# series_noprotection.net
KiCad netlist of a schematic drawn in Altium Designer
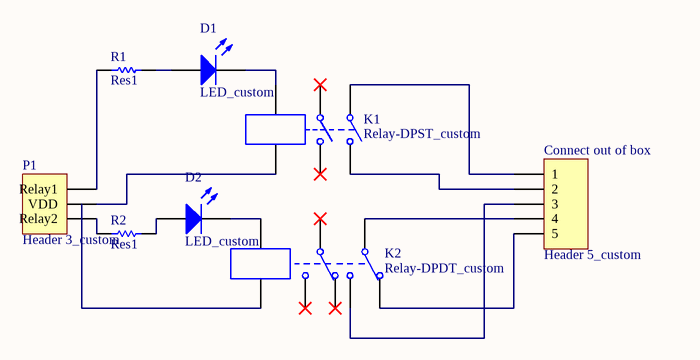
[diagram p0: series_noprotection.SchDoc]

(export (version "E")
  (design (tool "Eeschema 10.0.6"))
  (components
    (comp (ref "Connect out of box")
      (value "Header 5_custom")
      (footprint "PCB_Footprints:TE5")
      (description "Header, 5-Pin")
      (fields (field (name "PUBLISHER") "Altium Limited"))
      (libsource (lib "Integrated_Library_1") (part "Header 5_custom"))
    )
    (comp (ref "D1")
      (value "LED_custom")
      (footprint "PCB_Footprints:LED_Custom")
      (description "Typical INFRARED GaAs LED")
      (fields (field (name "PUBLISHER") "Altium Limited"))
      (libsource (lib "Integrated_Library_1") (part "LED_custom"))
    )
    (comp (ref "D2")
      (value "LED_custom")
      (footprint "PCB_Footprints:LED_Custom")
      (description "Typical INFRARED GaAs LED")
      (fields (field (name "PUBLISHER") "Altium Limited"))
      (libsource (lib "Integrated_Library_1") (part "LED_custom"))
    )
    (comp (ref "K1")
      (value "Relay-DPST_custom")
      (footprint "Relay-DPST_custom")
      (description "Dual-Pole Single-Throw Relay")
      (fields (field (name "PUBLISHER") "Altium Limited"))
      (libsource (lib "Integrated_Library_1") (part "Relay-DPST_custom"))
    )
    (comp (ref "K2")
      (value "Relay-DPDT_custom")
      (footprint "Relay-DPDT_custom")
      (description "Dual-Pole Dual-Throw Relay")
      (fields (field (name "PUBLISHER") "Altium Limited"))
      (libsource (lib "Integrated_Library_1") (part "Relay-DPDT_custom"))
    )
    (comp (ref "P1")
      (value "Header 3_custom")
      (footprint "PCB_Footprints:TB3")
      (description "Header, 3-Pin")
      (fields (field (name "PUBLISHER") "Altium Limited"))
      (libsource (lib "Integrated_Library_1") (part "Header 3_custom"))
    )
    (comp (ref "R1")
      (value "Res1")
      (footprint "AXIAL-0.3")
      (description "Resistor")
      (fields (field (name "PUBLISHER") "Altium Limited"))
      (libsource (lib "Miscellaneous Devices") (part "Res1"))
    )
    (comp (ref "R2")
      (value "Res1")
      (footprint "AXIAL-0.3")
      (description "Resistor")
      (fields (field (name "PUBLISHER") "Altium Limited"))
      (libsource (lib "Miscellaneous Devices") (part "Res1"))
    )
  )
  (nets
    (net (code "1") (name "Net-(Connect out of box-Pad1)") (class "Default")
      (node (ref "Connect out of box") (pin "1") (pinfunction "1_1") (pintype "passive"))
      (node (ref "K1") (pin "1") (pinfunction "1_1") (pintype "passive"))
    )
    (net (code "2") (name "Net-(Connect out of box-Pad2)") (class "Default")
      (node (ref "Connect out of box") (pin "2") (pinfunction "2_2") (pintype "passive"))
      (node (ref "K1") (pin "2") (pinfunction "2_2") (pintype "passive"))
    )
    (net (code "3") (name "Net-(Connect out of box-Pad3)") (class "Default")
      (node (ref "Connect out of box") (pin "3") (pinfunction "3_3") (pintype "passive"))
      (node (ref "K2") (pin "3") (pinfunction "3_3") (pintype "passive"))
    )
    (net (code "4") (name "Net-(Connect out of box-Pad4)") (class "Default")
      (node (ref "Connect out of box") (pin "4") (pinfunction "4_4") (pintype "passive"))
      (node (ref "K2") (pin "1") (pinfunction "1_1") (pintype "passive"))
    )
    (net (code "5") (name "Net-(Connect out of box-Pad5)") (class "Default")
      (node (ref "Connect out of box") (pin "5") (pinfunction "5_5") (pintype "passive"))
      (node (ref "K2") (pin "2") (pinfunction "2_2") (pintype "passive"))
    )
    (net (code "6") (name "Net-(D1-A)") (class "Default")
      (node (ref "D1") (pin "1") (pinfunction "A_1") (pintype "passive"))
      (node (ref "R1") (pin "1") (pinfunction "1_1") (pintype "passive"))
    )
    (net (code "7") (name "Net-(D1-K)") (class "Default")
      (node (ref "D1") (pin "2") (pinfunction "K_2") (pintype "passive"))
      (node (ref "K1") (pin "5") (pinfunction "5_5") (pintype "passive"))
    )
    (net (code "8") (name "Net-(D2-A)") (class "Default")
      (node (ref "D2") (pin "1") (pinfunction "A_1") (pintype "passive"))
      (node (ref "R2") (pin "1") (pinfunction "1_1") (pintype "passive"))
    )
    (net (code "9") (name "Net-(D2-K)") (class "Default")
      (node (ref "D2") (pin "2") (pinfunction "K_2") (pintype "passive"))
      (node (ref "K2") (pin "7") (pinfunction "7_7") (pintype "passive"))
    )
    (net (code "10") (name "Net-(P1-Relay1)") (class "Default")
      (node (ref "P1") (pin "3") (pinfunction "Relay1_3") (pintype "passive"))
      (node (ref "R1") (pin "2") (pinfunction "2_2") (pintype "passive"))
    )
    (net (code "11") (name "Net-(P1-Relay2)") (class "Default")
      (node (ref "P1") (pin "1") (pinfunction "Relay2_1") (pintype "passive"))
      (node (ref "R2") (pin "2") (pinfunction "2_2") (pintype "passive"))
    )
    (net (code "12") (name "Net-(P1-VDD)") (class "Default")
      (node (ref "K1") (pin "6") (pinfunction "6_6") (pintype "passive"))
      (node (ref "P1") (pin "2") (pinfunction "VDD_2") (pintype "passive"))
    )
    (net (code "13") (name "unconnected-(K1-Pad3)") (class "Default")
      (node (ref "K1") (pin "3") (pinfunction "3_3") (pintype "passive+no_connect"))
    )
    (net (code "14") (name "unconnected-(K1-Pad4)") (class "Default")
      (node (ref "K1") (pin "4") (pinfunction "4_4") (pintype "passive+no_connect"))
    )
    (net (code "15") (name "unconnected-(K2-Pad4)") (class "Default")
      (node (ref "K2") (pin "4") (pinfunction "4_4") (pintype "passive+no_connect"))
    )
    (net (code "16") (name "unconnected-(K2-Pad5)") (class "Default")
      (node (ref "K2") (pin "5") (pinfunction "5_5") (pintype "passive+no_connect"))
    )
    (net (code "17") (name "unconnected-(K2-Pad6)") (class "Default")
      (node (ref "K2") (pin "6") (pinfunction "6_6") (pintype "passive+no_connect"))
    )
    (net (code "18") (name "unconnected-(K2-Pad8)") (class "Default")
      (node (ref "K2") (pin "8") (pinfunction "8_8") (pintype "passive"))
    )
  )
)
